# POWER.net
KiCad netlist of a schematic drawn in Altium Designer
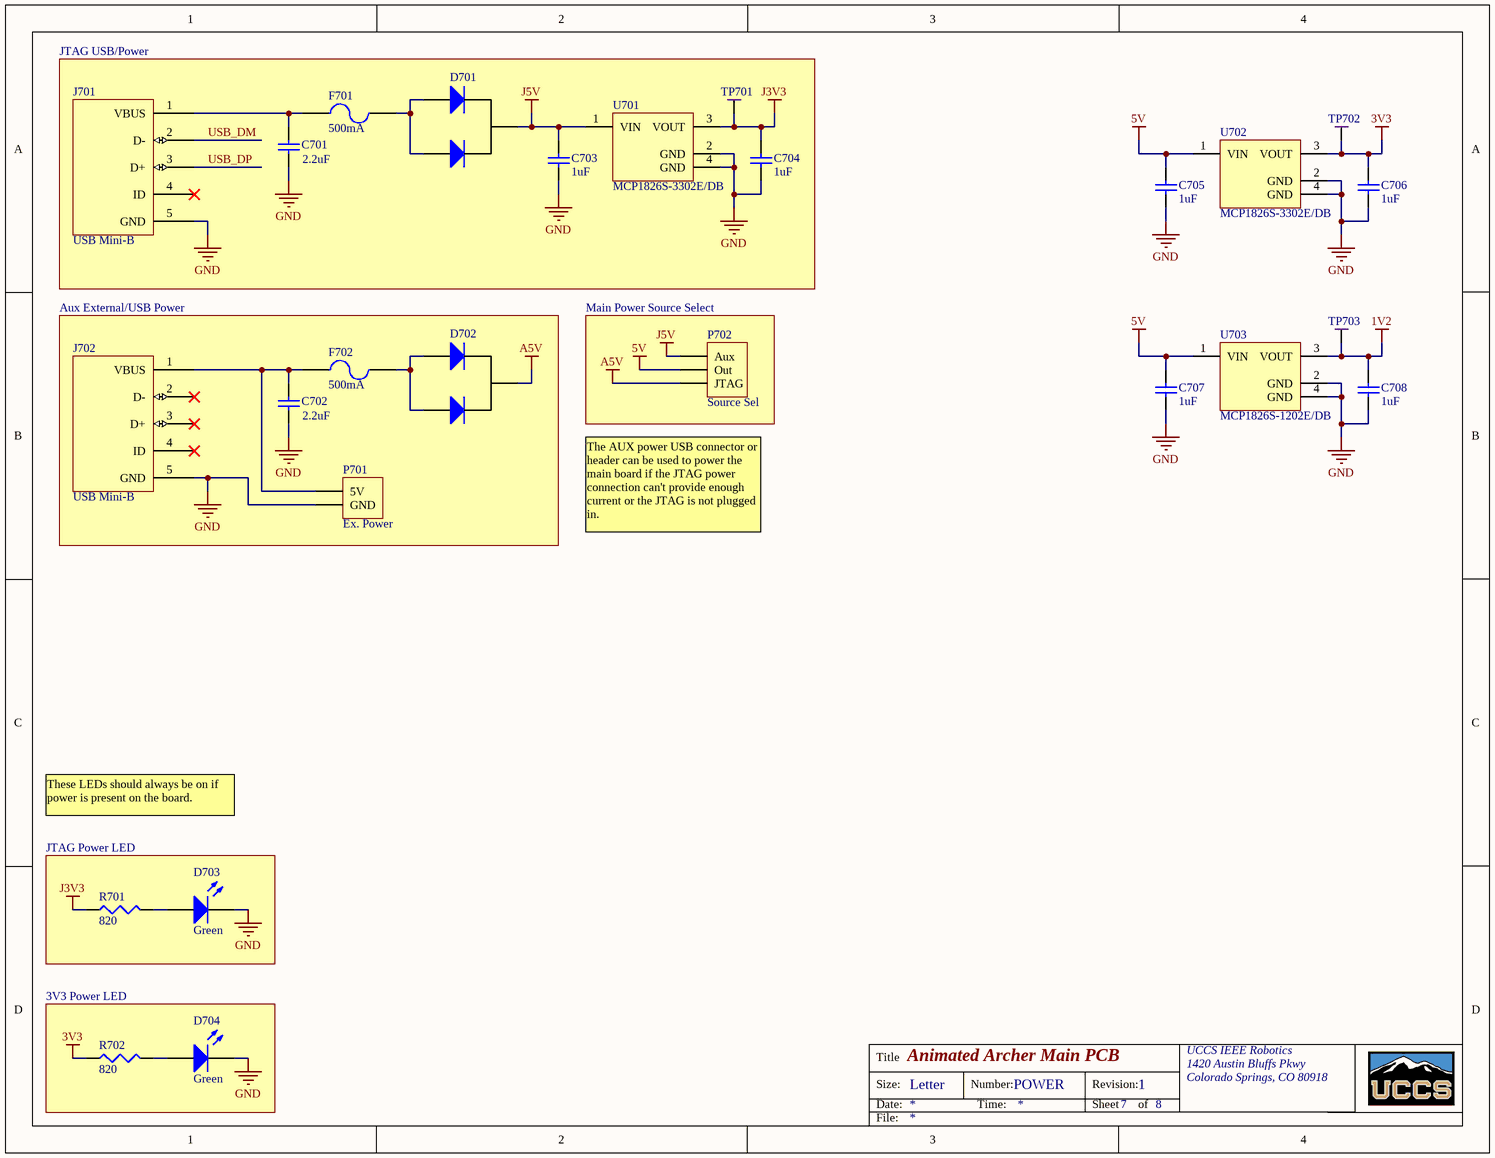
[diagram p0: POWER.SchDoc]

(export (version "E")
  (design (tool "Eeschema 10.0.6"))
  (components
    (comp (ref "C701")
      (value "2.2uF")
      (footprint "1608[0603]")
      (description "Capacitor (Semiconductor SIM Model)")
      (fields (field (name "Comment") "Cap Semi") (field (name "PUBLISHER") "Altium Limited"))
      (libsource (lib "Miscellaneous Devices") (part "Cap Semi"))
    )
    (comp (ref "C702")
      (value "2.2uF")
      (footprint "1608[0603]")
      (description "Capacitor (Semiconductor SIM Model)")
      (fields (field (name "Comment") "Cap Semi") (field (name "PUBLISHER") "Altium Limited"))
      (libsource (lib "Miscellaneous Devices") (part "Cap Semi"))
    )
    (comp (ref "C703")
      (value "1uF")
      (footprint "1608[0603]")
      (description "Capacitor (Semiconductor SIM Model)")
      (fields (field (name "Comment") "0.1uF") (field (name "PUBLISHER") "Altium Limited"))
      (libsource (lib "Miscellaneous Devices") (part "Cap Semi"))
    )
    (comp (ref "C704")
      (value "1uF")
      (footprint "1608[0603]")
      (description "Capacitor (Semiconductor SIM Model)")
      (fields (field (name "Comment") "0.1uF") (field (name "PUBLISHER") "Altium Limited"))
      (libsource (lib "Miscellaneous Devices") (part "Cap Semi"))
    )
    (comp (ref "C705")
      (value "1uF")
      (footprint "1608[0603]")
      (description "Capacitor (Semiconductor SIM Model)")
      (fields (field (name "Comment") "0.1uF") (field (name "PUBLISHER") "Altium Limited"))
      (libsource (lib "Miscellaneous Devices") (part "Cap Semi"))
    )
    (comp (ref "C706")
      (value "1uF")
      (footprint "1608[0603]")
      (description "Capacitor (Semiconductor SIM Model)")
      (fields (field (name "Comment") "0.1uF") (field (name "PUBLISHER") "Altium Limited"))
      (libsource (lib "Miscellaneous Devices") (part "Cap Semi"))
    )
    (comp (ref "C707")
      (value "1uF")
      (footprint "1608[0603]")
      (description "Capacitor (Semiconductor SIM Model)")
      (fields (field (name "Comment") "0.1uF") (field (name "PUBLISHER") "Altium Limited"))
      (libsource (lib "Miscellaneous Devices") (part "Cap Semi"))
    )
    (comp (ref "C708")
      (value "1uF")
      (footprint "1608[0603]")
      (description "Capacitor (Semiconductor SIM Model)")
      (fields (field (name "Comment") "0.1uF") (field (name "PUBLISHER") "Altium Limited"))
      (libsource (lib "Miscellaneous Devices") (part "Cap Semi"))
    )
    (comp (ref "D701")
      (value "HSMS-2804-BLKG")
      (footprint "SOT-23_N")
      (description "Dual Common Cathode Schottky Diode")
      (fields (field (name "PUBLISHER") "Altium Limited"))
      (libsource (lib "Image Vortex Rev4") (part "HSMS-2804-BLKG"))
    )
    (comp (ref "D702")
      (value "HSMS-2804-BLKG")
      (footprint "SOT-23_N")
      (description "Dual Common Cathode Schottky Diode")
      (fields (field (name "PUBLISHER") "Altium Limited"))
      (libsource (lib "Image Vortex Rev4") (part "HSMS-2804-BLKG"))
    )
    (comp (ref "D703")
      (value "Green")
      (footprint "1608[0603]")
      (description "Typical RED, GREEN, YELLOW, AMBER GaAs LED")
      (fields (field (name "PUBLISHER") "Altium Limited"))
      (libsource (lib "Miscellaneous Devices") (part "LED2"))
    )
    (comp (ref "D704")
      (value "Green")
      (footprint "1608[0603]")
      (description "Typical RED, GREEN, YELLOW, AMBER GaAs LED")
      (fields (field (name "PUBLISHER") "Altium Limited"))
      (libsource (lib "Miscellaneous Devices") (part "LED2"))
    )
    (comp (ref "F701")
      (value "500mA")
      (footprint "C0805")
      (description "PTC Resettable Fuse")
      (fields (field (name "PUBLISHER") "Altium Limited"))
      (libsource (lib "Miscellaneous Devices") (part "Fuse 2"))
    )
    (comp (ref "F702")
      (value "500mA")
      (footprint "C0805")
      (description "PTC Resettable Fuse")
      (fields (field (name "PUBLISHER") "Altium Limited"))
      (libsource (lib "Miscellaneous Devices") (part "Fuse 2"))
    )
    (comp (ref "J701")
      (value "USB Mini-B")
      (footprint "54819-0572")
      (description "54819-0572")
      (libsource (lib "Animated Archer") (part "USB Mini-B"))
    )
    (comp (ref "J702")
      (value "USB Mini-B")
      (footprint "54819-0572")
      (description "54819-0572")
      (libsource (lib "Animated Archer") (part "USB Mini-B"))
    )
    (comp (ref "P701")
      (value "Ex. Power")
      (footprint "HDR1X2")
      (description "Header, 2-Pin")
      (fields (field (name "PUBLISHER") "Altium Limited"))
      (libsource (lib "Miscellaneous Connectors") (part "Header 2"))
    )
    (comp (ref "P702")
      (value "Source Sel")
      (footprint "HDR1X3")
      (description "Header, 3-Pin")
      (fields (field (name "PUBLISHER") "Altium Limited"))
      (libsource (lib "Miscellaneous Connectors") (part "Header 3"))
    )
    (comp (ref "R701")
      (value "820")
      (footprint "J1-0603")
      (description "Resistor")
      (fields (field (name "Comment") "Res3") (field (name "PUBLISHER") "Altium Limited"))
      (libsource (lib "Miscellaneous Devices") (part "Res3"))
    )
    (comp (ref "R702")
      (value "820")
      (footprint "J1-0603")
      (description "Resistor")
      (fields (field (name "Comment") "Res3") (field (name "PUBLISHER") "Altium Limited"))
      (libsource (lib "Miscellaneous Devices") (part "Res3"))
    )
    (comp (ref "TP701")
      (value "Test Point")
      (footprint "TESTPT")
      (libsource (lib "Animated Archer") (part "Test Point"))
    )
    (comp (ref "TP702")
      (value "Test Point")
      (footprint "TESTPT")
      (libsource (lib "Animated Archer") (part "Test Point"))
    )
    (comp (ref "TP703")
      (value "Test Point")
      (footprint "TESTPT")
      (libsource (lib "Animated Archer") (part "Test Point"))
    )
    (comp (ref "U701")
      (value "MCP1826S-3302E/DB")
      (footprint "SOT-223-DB3_N")
      (description "1000 mA, Low Voltage, Low Quiescent Current LDO Regulator, 3-Pin SOT-223, Extended Temperature")
      (fields (field (name "PUBLISHER") "Altium Limited"))
      (libsource (lib "Animated Archer") (part "MCP1826S-3302E/DB"))
    )
    (comp (ref "U702")
      (value "MCP1826S-3302E/DB")
      (footprint "SOT-223-DB3_N")
      (description "1000 mA, Low Voltage, Low Quiescent Current LDO Regulator, 3-Pin SOT-223, Extended Temperature")
      (fields (field (name "PUBLISHER") "Altium Limited"))
      (libsource (lib "Animated Archer") (part "MCP1826S-3302E/DB"))
    )
    (comp (ref "U703")
      (value "MCP1826S-1202E/DB")
      (footprint "SOT-223-DB3_N")
      (description "1000 mA, Low Voltage, Low Quiescent Current LDO Regulator, 3-Pin SOT-223, Extended Temperature")
      (fields (field (name "PUBLISHER") "Altium Limited"))
      (libsource (lib "Animated Archer") (part "MCP1826S-1202E/DB"))
    )
  )
  (nets
    (net (code "1") (name "/USB_DM") (class "Default")
      (node (ref "J701") (pin "2") (pinfunction "D-_2") (pintype "bidirectional"))
    )
    (net (code "2") (name "/USB_DP") (class "Default")
      (node (ref "J701") (pin "3") (pinfunction "D+_3") (pintype "bidirectional"))
    )
    (net (code "3") (name "1V2") (class "Default")
      (node (ref "C708") (pin "2") (pinfunction "2_2") (pintype "passive"))
      (node (ref "TP703") (pin "1") (pinfunction "1_1") (pintype "passive"))
      (node (ref "U703") (pin "3") (pinfunction "VOUT_3") (pintype "power_in"))
    )
    (net (code "4") (name "3V3") (class "Default")
      (node (ref "C706") (pin "2") (pinfunction "2_2") (pintype "passive"))
      (node (ref "R702") (pin "1") (pinfunction "1_1") (pintype "passive"))
      (node (ref "TP702") (pin "1") (pinfunction "1_1") (pintype "passive"))
      (node (ref "U702") (pin "3") (pinfunction "VOUT_3") (pintype "power_in"))
    )
    (net (code "5") (name "5V") (class "Default")
      (node (ref "C705") (pin "2") (pinfunction "2_2") (pintype "passive"))
      (node (ref "C707") (pin "2") (pinfunction "2_2") (pintype "passive"))
      (node (ref "P702") (pin "2") (pinfunction "Out_2") (pintype "passive"))
      (node (ref "U702") (pin "1") (pinfunction "VIN_1") (pintype "power_in"))
      (node (ref "U703") (pin "1") (pinfunction "VIN_1") (pintype "power_in"))
    )
    (net (code "6") (name "A5V") (class "Default")
      (node (ref "D702") (pin "3") (pinfunction "K_3") (pintype "passive"))
      (node (ref "P702") (pin "3") (pinfunction "JTAG_3") (pintype "passive"))
    )
    (net (code "7") (name "GND") (class "Default")
      (node (ref "C701") (pin "2") (pinfunction "2_2") (pintype "passive"))
      (node (ref "C702") (pin "2") (pinfunction "2_2") (pintype "passive"))
      (node (ref "C703") (pin "1") (pinfunction "1_1") (pintype "passive"))
      (node (ref "C704") (pin "1") (pinfunction "1_1") (pintype "passive"))
      (node (ref "C705") (pin "1") (pinfunction "1_1") (pintype "passive"))
      (node (ref "C706") (pin "1") (pinfunction "1_1") (pintype "passive"))
      (node (ref "C707") (pin "1") (pinfunction "1_1") (pintype "passive"))
      (node (ref "C708") (pin "1") (pinfunction "1_1") (pintype "passive"))
      (node (ref "D703") (pin "2") (pinfunction "K_2") (pintype "passive"))
      (node (ref "D704") (pin "2") (pinfunction "K_2") (pintype "passive"))
      (node (ref "J701") (pin "5") (pinfunction "GND_5") (pintype "power_in"))
      (node (ref "J702") (pin "5") (pinfunction "GND_5") (pintype "power_in"))
      (node (ref "P701") (pin "2") (pinfunction "GND_2") (pintype "passive"))
      (node (ref "U701") (pin "2") (pinfunction "GND_2") (pintype "power_in"))
      (node (ref "U701") (pin "4") (pinfunction "GND_4") (pintype "power_in"))
      (node (ref "U702") (pin "2") (pinfunction "GND_2") (pintype "power_in"))
      (node (ref "U702") (pin "4") (pinfunction "GND_4") (pintype "power_in"))
      (node (ref "U703") (pin "2") (pinfunction "GND_2") (pintype "power_in"))
      (node (ref "U703") (pin "4") (pinfunction "GND_4") (pintype "power_in"))
    )
    (net (code "8") (name "J3V3") (class "Default")
      (node (ref "C704") (pin "2") (pinfunction "2_2") (pintype "passive"))
      (node (ref "R701") (pin "1") (pinfunction "1_1") (pintype "passive"))
      (node (ref "TP701") (pin "1") (pinfunction "1_1") (pintype "passive"))
      (node (ref "U701") (pin "3") (pinfunction "VOUT_3") (pintype "power_in"))
    )
    (net (code "9") (name "J5V") (class "Default")
      (node (ref "C703") (pin "2") (pinfunction "2_2") (pintype "passive"))
      (node (ref "D701") (pin "3") (pinfunction "K_3") (pintype "passive"))
      (node (ref "P702") (pin "1") (pinfunction "Aux_1") (pintype "passive"))
      (node (ref "U701") (pin "1") (pinfunction "VIN_1") (pintype "power_in"))
    )
    (net (code "10") (name "Net-(D701-A)") (class "Default")
      (node (ref "D701") (pin "1") (pinfunction "A_1") (pintype "passive"))
      (node (ref "D701") (pin "2") (pinfunction "B_2") (pintype "passive"))
      (node (ref "F701") (pin "1") (pinfunction "1_1") (pintype "passive"))
    )
    (net (code "11") (name "Net-(D702-A)") (class "Default")
      (node (ref "D702") (pin "1") (pinfunction "A_1") (pintype "passive"))
      (node (ref "D702") (pin "2") (pinfunction "B_2") (pintype "passive"))
      (node (ref "F702") (pin "1") (pinfunction "1_1") (pintype "passive"))
    )
    (net (code "12") (name "Net-(D703-A)") (class "Default")
      (node (ref "D703") (pin "1") (pinfunction "A_1") (pintype "passive"))
      (node (ref "R701") (pin "2") (pinfunction "2_2") (pintype "passive"))
    )
    (net (code "13") (name "Net-(D704-A)") (class "Default")
      (node (ref "D704") (pin "1") (pinfunction "A_1") (pintype "passive"))
      (node (ref "R702") (pin "2") (pinfunction "2_2") (pintype "passive"))
    )
    (net (code "14") (name "Net-(J701-VBUS)") (class "Default")
      (node (ref "C701") (pin "1") (pinfunction "1_1") (pintype "passive"))
      (node (ref "F701") (pin "2") (pinfunction "2_2") (pintype "passive"))
      (node (ref "J701") (pin "1") (pinfunction "VBUS_1") (pintype "power_in"))
    )
    (net (code "15") (name "Net-(J702-VBUS)") (class "Default")
      (node (ref "C702") (pin "1") (pinfunction "1_1") (pintype "passive"))
      (node (ref "F702") (pin "2") (pinfunction "2_2") (pintype "passive"))
      (node (ref "J702") (pin "1") (pinfunction "VBUS_1") (pintype "power_in"))
      (node (ref "P701") (pin "1") (pinfunction "5V_1") (pintype "passive"))
    )
    (net (code "16") (name "unconnected-(J701-CASE-Pad6)") (class "Default")
      (node (ref "J701") (pin "6") (pinfunction "CASE_6") (pintype "passive"))
    )
    (net (code "17") (name "unconnected-(J701-ID-Pad4)") (class "Default")
      (node (ref "J701") (pin "4") (pinfunction "ID_4") (pintype "passive+no_connect"))
    )
    (net (code "18") (name "unconnected-(J702-CASE-Pad6)") (class "Default")
      (node (ref "J702") (pin "6") (pinfunction "CASE_6") (pintype "passive"))
    )
    (net (code "19") (name "unconnected-(J702-D+-Pad3)") (class "Default")
      (node (ref "J702") (pin "3") (pinfunction "D+_3") (pintype "bidirectional+no_connect"))
    )
    (net (code "20") (name "unconnected-(J702-D--Pad2)") (class "Default")
      (node (ref "J702") (pin "2") (pinfunction "D-_2") (pintype "bidirectional+no_connect"))
    )
    (net (code "21") (name "unconnected-(J702-ID-Pad4)") (class "Default")
      (node (ref "J702") (pin "4") (pinfunction "ID_4") (pintype "passive+no_connect"))
    )
  )
)
